# 7-segment.net
KiCad netlist of a schematic drawn in EAGLE
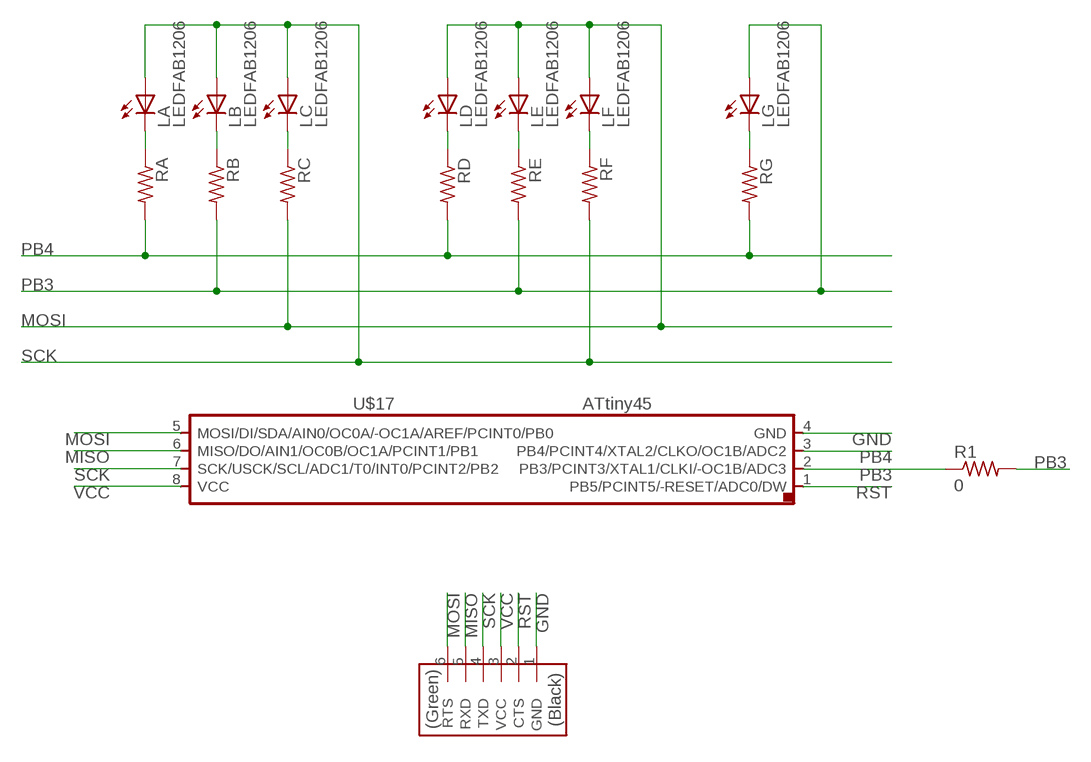
[diagram p0: schematic, sheet 1]

(export (version "E")
  (design (tool "Eeschema 10.0.6"))
  (components
    (comp (ref "LA")
      (value "LEDFAB1206")
      (footprint "eagle-import:LED1206FAB")
      (libsource (lib "eagle-import") (part "LEDFAB1206"))
    )
    (comp (ref "LB")
      (value "LEDFAB1206")
      (footprint "eagle-import:LED1206FAB")
      (libsource (lib "eagle-import") (part "LEDFAB1206"))
    )
    (comp (ref "LC")
      (value "LEDFAB1206")
      (footprint "eagle-import:LED1206FAB")
      (libsource (lib "eagle-import") (part "LEDFAB1206"))
    )
    (comp (ref "LD")
      (value "LEDFAB1206")
      (footprint "eagle-import:LED1206FAB")
      (libsource (lib "eagle-import") (part "LEDFAB1206"))
    )
    (comp (ref "LE")
      (value "LEDFAB1206")
      (footprint "eagle-import:LED1206FAB")
      (libsource (lib "eagle-import") (part "LEDFAB1206"))
    )
    (comp (ref "LF")
      (value "LEDFAB1206")
      (footprint "eagle-import:LED1206FAB")
      (libsource (lib "eagle-import") (part "LEDFAB1206"))
    )
    (comp (ref "LG")
      (value "LEDFAB1206")
      (footprint "eagle-import:LED1206FAB")
      (libsource (lib "eagle-import") (part "LEDFAB1206"))
    )
    (comp (ref "R1")
      (value "0")
      (footprint "eagle-import:R1206FAB")
      (libsource (lib "eagle-import") (part "RES-US1206FAB"))
    )
    (comp (ref "RA")
      (value "RES-US1206FAB")
      (footprint "eagle-import:R1206FAB")
      (libsource (lib "eagle-import") (part "RES-US1206FAB"))
    )
    (comp (ref "RB")
      (value "RES-US1206FAB")
      (footprint "eagle-import:R1206FAB")
      (libsource (lib "eagle-import") (part "RES-US1206FAB"))
    )
    (comp (ref "RC")
      (value "RES-US1206FAB")
      (footprint "eagle-import:R1206FAB")
      (libsource (lib "eagle-import") (part "RES-US1206FAB"))
    )
    (comp (ref "RD")
      (value "RES-US1206FAB")
      (footprint "eagle-import:R1206FAB")
      (libsource (lib "eagle-import") (part "RES-US1206FAB"))
    )
    (comp (ref "RE")
      (value "RES-US1206FAB")
      (footprint "eagle-import:R1206FAB")
      (libsource (lib "eagle-import") (part "RES-US1206FAB"))
    )
    (comp (ref "RF")
      (value "RES-US1206FAB")
      (footprint "eagle-import:R1206FAB")
      (libsource (lib "eagle-import") (part "RES-US1206FAB"))
    )
    (comp (ref "RG")
      (value "RES-US1206FAB")
      (footprint "eagle-import:R1206FAB")
      (libsource (lib "eagle-import") (part "RES-US1206FAB"))
    )
    (comp (ref "U$3")
      (value "FTDI-SMD-HEADER")
      (footprint "eagle-import:1X06SMD")
      (libsource (lib "eagle-import") (part "FTDI-SMD-HEADER"))
    )
    (comp (ref "U$17")
      (value "ATTINY45SI")
      (footprint "eagle-import:SOIC8")
      (libsource (lib "eagle-import") (part "ATTINY45SI"))
    )
  )
  (nets
    (net (code "1") (name "/GND") (class "Default")
      (node (ref "U$17") (pin "4") (pinfunction "GND_4") (pintype "bidirectional"))
      (node (ref "U$3") (pin "1") (pinfunction "GND_1") (pintype "bidirectional"))
    )
    (net (code "2") (name "/MISO") (class "Default")
      (node (ref "U$17") (pin "6") (pinfunction "MISO/DO/AIN1/OC0B/OC1A/PCINT1/PB1_6") (pintype "bidirectional"))
      (node (ref "U$3") (pin "5") (pinfunction "RXD_5") (pintype "bidirectional"))
    )
    (net (code "3") (name "/MOSI") (class "Default")
      (node (ref "LD") (pin "1") (pinfunction "A_1") (pintype "passive"))
      (node (ref "LE") (pin "1") (pinfunction "A_1") (pintype "passive"))
      (node (ref "LF") (pin "1") (pinfunction "A_1") (pintype "passive"))
      (node (ref "RC") (pin "2") (pinfunction "2_2") (pintype "passive"))
      (node (ref "U$17") (pin "5") (pinfunction "MOSI/DI/SDA/AIN0/OC0A/-OC1A/AREF/PCINT0/PB0_5") (pintype "bidirectional"))
      (node (ref "U$3") (pin "6") (pinfunction "RTS_6") (pintype "bidirectional"))
    )
    (net (code "4") (name "/PB3") (class "Default")
      (node (ref "LG") (pin "1") (pinfunction "A_1") (pintype "passive"))
      (node (ref "R1") (pin "1") (pinfunction "1_1") (pintype "passive"))
      (node (ref "R1") (pin "2") (pinfunction "2_2") (pintype "passive"))
      (node (ref "RB") (pin "2") (pinfunction "2_2") (pintype "passive"))
      (node (ref "RE") (pin "2") (pinfunction "2_2") (pintype "passive"))
      (node (ref "U$17") (pin "2") (pinfunction "PB3/PCINT3/XTAL1/CLKI/-OC1B/ADC3_2") (pintype "bidirectional"))
    )
    (net (code "5") (name "/PB4") (class "Default")
      (node (ref "RA") (pin "2") (pinfunction "2_2") (pintype "passive"))
      (node (ref "RD") (pin "2") (pinfunction "2_2") (pintype "passive"))
      (node (ref "RG") (pin "2") (pinfunction "2_2") (pintype "passive"))
      (node (ref "U$17") (pin "3") (pinfunction "PB4/PCINT4/XTAL2/CLKO/OC1B/ADC2_3") (pintype "bidirectional"))
    )
    (net (code "6") (name "/RST") (class "Default")
      (node (ref "U$17") (pin "1") (pinfunction "PB5/PCINT5/-RESET/ADC0/DW_1") (pintype "bidirectional"))
      (node (ref "U$3") (pin "2") (pinfunction "CTS_2") (pintype "bidirectional"))
    )
    (net (code "7") (name "/SCK") (class "Default")
      (node (ref "LA") (pin "1") (pinfunction "A_1") (pintype "passive"))
      (node (ref "LB") (pin "1") (pinfunction "A_1") (pintype "passive"))
      (node (ref "LC") (pin "1") (pinfunction "A_1") (pintype "passive"))
      (node (ref "RF") (pin "2") (pinfunction "2_2") (pintype "passive"))
      (node (ref "U$17") (pin "7") (pinfunction "SCK/USCK/SCL/ADC1/T0/INT0/PCINT2/PB2_7") (pintype "bidirectional"))
      (node (ref "U$3") (pin "4") (pinfunction "TXD_4") (pintype "bidirectional"))
    )
    (net (code "8") (name "/VCC") (class "Default")
      (node (ref "U$17") (pin "8") (pinfunction "VCC_8") (pintype "bidirectional"))
      (node (ref "U$3") (pin "3") (pinfunction "VCC_3") (pintype "bidirectional"))
    )
    (net (code "9") (name "Net-(LA-C)") (class "Default")
      (node (ref "LA") (pin "2") (pinfunction "C_2") (pintype "passive"))
      (node (ref "RA") (pin "1") (pinfunction "1_1") (pintype "passive"))
    )
    (net (code "10") (name "Net-(LB-C)") (class "Default")
      (node (ref "LB") (pin "2") (pinfunction "C_2") (pintype "passive"))
      (node (ref "RB") (pin "1") (pinfunction "1_1") (pintype "passive"))
    )
    (net (code "11") (name "Net-(LC-C)") (class "Default")
      (node (ref "LC") (pin "2") (pinfunction "C_2") (pintype "passive"))
      (node (ref "RC") (pin "1") (pinfunction "1_1") (pintype "passive"))
    )
    (net (code "12") (name "Net-(LD-C)") (class "Default")
      (node (ref "LD") (pin "2") (pinfunction "C_2") (pintype "passive"))
      (node (ref "RD") (pin "1") (pinfunction "1_1") (pintype "passive"))
    )
    (net (code "13") (name "Net-(LE-C)") (class "Default")
      (node (ref "LE") (pin "2") (pinfunction "C_2") (pintype "passive"))
      (node (ref "RE") (pin "1") (pinfunction "1_1") (pintype "passive"))
    )
    (net (code "14") (name "Net-(LF-C)") (class "Default")
      (node (ref "LF") (pin "2") (pinfunction "C_2") (pintype "passive"))
      (node (ref "RF") (pin "1") (pinfunction "1_1") (pintype "passive"))
    )
    (net (code "15") (name "Net-(LG-C)") (class "Default")
      (node (ref "LG") (pin "2") (pinfunction "C_2") (pintype "passive"))
      (node (ref "RG") (pin "1") (pinfunction "1_1") (pintype "passive"))
    )
  )
)
